# LoRa-Alarm.net
KiCad netlist of a schematic drawn in Altium Designer
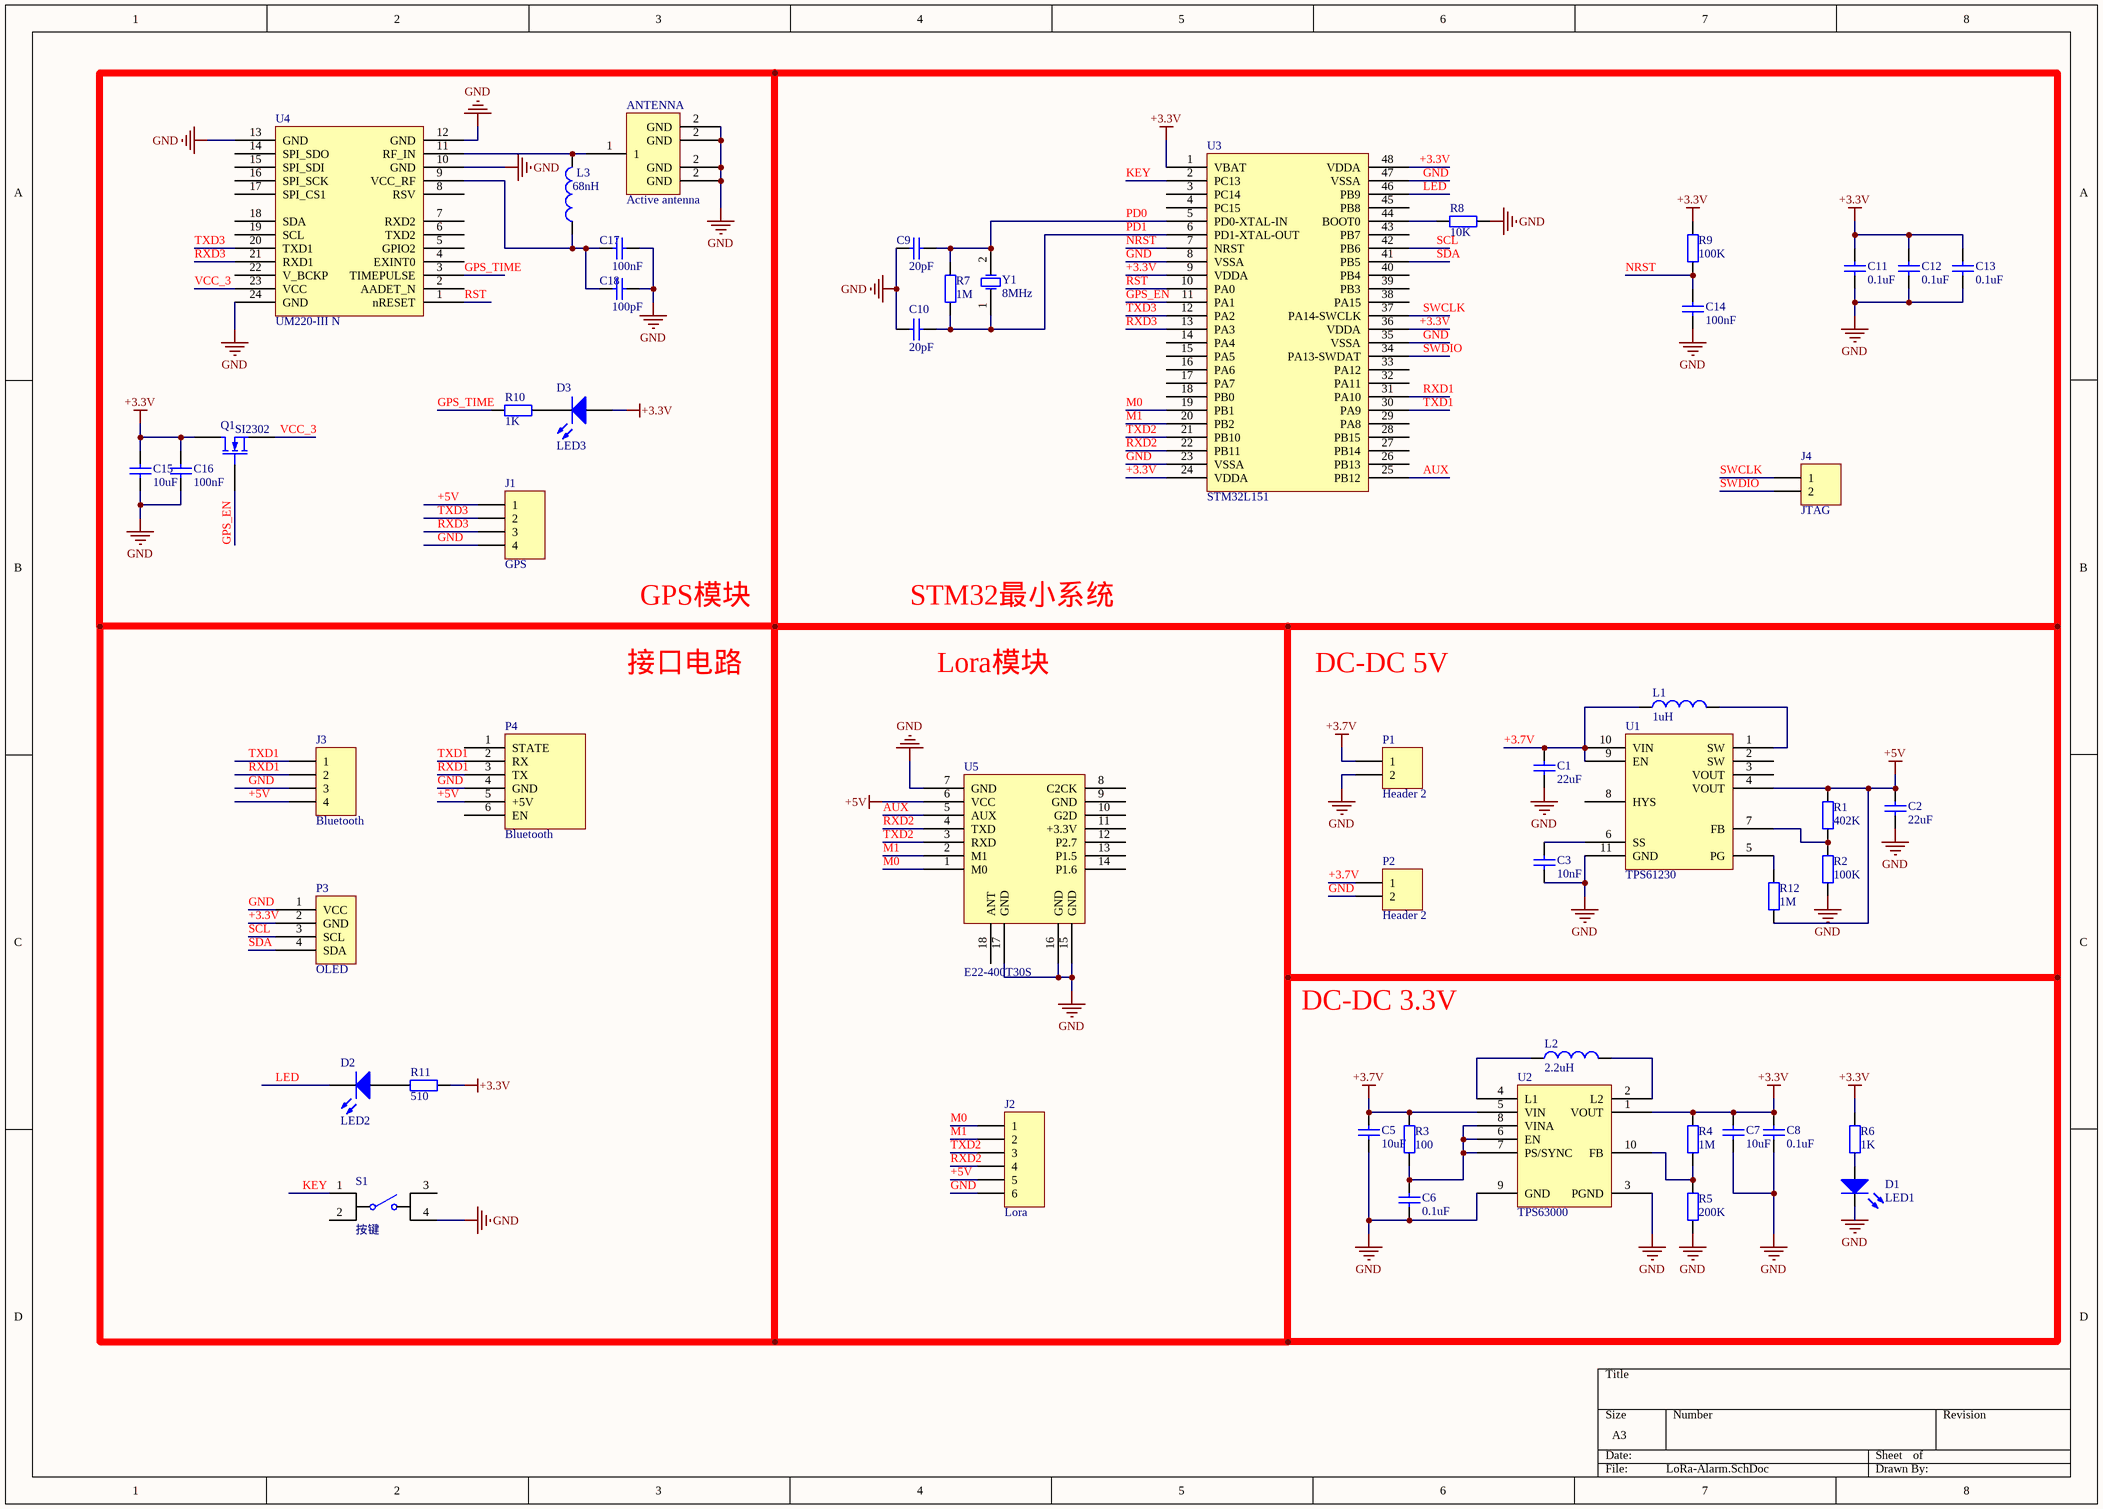
[diagram p0: LoRa-Alarm.SchDoc]

(export (version "E")
  (design (tool "Eeschema 10.0.6"))
  (components
    (comp (ref "ANTENNA")
      (value "Active antenna")
      (footprint "SMA-W")
      (libsource (lib "WuRenSouJiu") (part "Active antenna"))
    )
    (comp (ref "C1")
      (value "22uF")
      (footprint "0603C")
      (description "Capacitor")
      (fields (field (name "Comment") "Cap1") (field (name "PUBLISHER") "Altium Limited"))
      (libsource (lib "Miscellaneous Devices") (part "Cap"))
    )
    (comp (ref "C2")
      (value "22uF")
      (footprint "0603C")
      (description "Capacitor")
      (fields (field (name "Comment") "Cap2") (field (name "PUBLISHER") "Altium Limited"))
      (libsource (lib "Miscellaneous Devices") (part "Cap"))
    )
    (comp (ref "C3")
      (value "10nF")
      (footprint "0603C")
      (description "Capacitor")
      (fields (field (name "Comment") "Cap3") (field (name "PUBLISHER") "Altium Limited"))
      (libsource (lib "Miscellaneous Devices") (part "Cap"))
    )
    (comp (ref "C5")
      (value "10uF")
      (footprint "0603C")
      (description "Capacitor")
      (fields (field (name "Comment") "Cap5") (field (name "PUBLISHER") "Altium Limited"))
      (libsource (lib "Miscellaneous Devices") (part "Cap"))
    )
    (comp (ref "C6")
      (value "0.1uF")
      (footprint "0603C")
      (description "Capacitor")
      (fields (field (name "Comment") "Cap6") (field (name "PUBLISHER") "Altium Limited"))
      (libsource (lib "Miscellaneous Devices") (part "Cap"))
    )
    (comp (ref "C7")
      (value "10uF")
      (footprint "0603C")
      (description "Capacitor")
      (fields (field (name "Comment") "Cap7") (field (name "PUBLISHER") "Altium Limited"))
      (libsource (lib "Miscellaneous Devices") (part "Cap"))
    )
    (comp (ref "C8")
      (value "0.1uF")
      (footprint "0603C")
      (description "Capacitor")
      (fields (field (name "Comment") "Cap8") (field (name "PUBLISHER") "Altium Limited"))
      (libsource (lib "Miscellaneous Devices") (part "Cap"))
    )
    (comp (ref "C9")
      (value "20pF")
      (footprint "0603C")
      (description "Capacitor")
      (fields (field (name "Comment") "Cap9") (field (name "PUBLISHER") "Altium Limited"))
      (libsource (lib "Miscellaneous Devices") (part "Cap"))
    )
    (comp (ref "C10")
      (value "20pF")
      (footprint "0603C")
      (description "Capacitor")
      (fields (field (name "Comment") "Cap10") (field (name "PUBLISHER") "Altium Limited"))
      (libsource (lib "Miscellaneous Devices") (part "Cap"))
    )
    (comp (ref "C11")
      (value "0.1uF")
      (footprint "0603C")
      (description "Capacitor")
      (fields (field (name "Comment") "Cap11") (field (name "PUBLISHER") "Altium Limited"))
      (libsource (lib "Miscellaneous Devices") (part "Cap"))
    )
    (comp (ref "C12")
      (value "0.1uF")
      (footprint "0603C")
      (description "Capacitor")
      (fields (field (name "Comment") "Cap12") (field (name "PUBLISHER") "Altium Limited"))
      (libsource (lib "Miscellaneous Devices") (part "Cap"))
    )
    (comp (ref "C13")
      (value "0.1uF")
      (footprint "0603C")
      (description "Capacitor")
      (fields (field (name "Comment") "Cap13") (field (name "PUBLISHER") "Altium Limited"))
      (libsource (lib "Miscellaneous Devices") (part "Cap"))
    )
    (comp (ref "C14")
      (value "100nF")
      (footprint "0603C")
      (description "Capacitor")
      (fields (field (name "Comment") "Cap14") (field (name "PUBLISHER") "Altium Limited"))
      (libsource (lib "Miscellaneous Devices") (part "Cap"))
    )
    (comp (ref "C15")
      (value "10uF")
      (footprint "0603C")
      (description "Capacitor")
      (fields (field (name "Comment") "Cap15") (field (name "PUBLISHER") "Altium Limited"))
      (libsource (lib "Miscellaneous Devices") (part "Cap"))
    )
    (comp (ref "C16")
      (value "100nF")
      (footprint "0603C")
      (description "Capacitor")
      (fields (field (name "Comment") "Cap16") (field (name "PUBLISHER") "Altium Limited"))
      (libsource (lib "Miscellaneous Devices") (part "Cap"))
    )
    (comp (ref "C17")
      (value "100nF")
      (footprint "0603C")
      (description "Capacitor")
      (fields (field (name "Comment") "Cap17") (field (name "PUBLISHER") "Altium Limited"))
      (libsource (lib "Miscellaneous Devices") (part "Cap"))
    )
    (comp (ref "C18")
      (value "100pF")
      (footprint "0603C")
      (description "Capacitor")
      (fields (field (name "Comment") "Cap18") (field (name "PUBLISHER") "Altium Limited"))
      (libsource (lib "Miscellaneous Devices") (part "Cap"))
    )
    (comp (ref "D1")
      (value "LED1")
      (footprint "贴片二极管")
      (description "Typical RED GaAs LED")
      (fields (field (name "PUBLISHER") "Altium Limited"))
      (libsource (lib "Miscellaneous Devices") (part "LED1"))
    )
    (comp (ref "D2")
      (value "LED2")
      (footprint "贴片二极管")
      (description "Typical RED GaAs LED")
      (fields (field (name "PUBLISHER") "Altium Limited"))
      (libsource (lib "Miscellaneous Devices") (part "LED1"))
    )
    (comp (ref "D3")
      (value "LED3")
      (footprint "贴片二极管")
      (description "Typical RED GaAs LED")
      (fields (field (name "PUBLISHER") "Altium Limited"))
      (libsource (lib "Miscellaneous Devices") (part "LED1"))
    )
    (comp (ref "J1")
      (value "GPS")
      (footprint "HDR1X4")
      (description "Header, 4-Pin")
      (fields (field (name "PUBLISHER") "Altium Limited"))
      (libsource (lib "Miscellaneous Connectors") (part "Header 4"))
    )
    (comp (ref "J2")
      (value "Lora")
      (footprint "HDR1X6")
      (description "Header, 6-Pin")
      (fields (field (name "PUBLISHER") "Altium Limited"))
      (libsource (lib "Miscellaneous Connectors") (part "Header 6"))
    )
    (comp (ref "J3")
      (value "Bluetooth")
      (footprint "HDR1X4")
      (description "Header, 4-Pin")
      (fields (field (name "PUBLISHER") "Altium Limited"))
      (libsource (lib "Miscellaneous Connectors") (part "Header 4"))
    )
    (comp (ref "J4")
      (value "JTAG")
      (footprint "HDR1X2")
      (description "Header, 2-Pin")
      (fields (field (name "PUBLISHER") "Altium Limited"))
      (libsource (lib "Miscellaneous Connectors") (part "Header 2"))
    )
    (comp (ref "L1")
      (value "1uH")
      (footprint "IND-SMD_L4.0-W4.0_SMNR4020")
      (description "Inductor")
      (fields (field (name "Comment") "Inductor1") (field (name "PUBLISHER") "Altium Limited"))
      (libsource (lib "Miscellaneous Devices") (part "Inductor"))
    )
    (comp (ref "L2")
      (value "2.2uH")
      (footprint "IND-SMD_L4.0-W4.0_SMNR4020")
      (description "Inductor")
      (fields (field (name "Comment") "Inductor2") (field (name "PUBLISHER") "Altium Limited"))
      (libsource (lib "Miscellaneous Devices") (part "Inductor"))
    )
    (comp (ref "L3")
      (value "68nH")
      (footprint "0603L")
      (description "Inductor")
      (fields (field (name "Comment") "Inductor3") (field (name "PUBLISHER") "Altium Limited"))
      (libsource (lib "Miscellaneous Devices") (part "Inductor"))
    )
    (comp (ref "P1")
      (value "Header 2")
      (footprint "HDR1X2")
      (description "Header, 2-Pin")
      (fields (field (name "PUBLISHER") "Altium Limited"))
      (libsource (lib "Miscellaneous Connectors") (part "Header 2"))
    )
    (comp (ref "P2")
      (value "Header 2")
      (footprint "HDR1X2")
      (description "Header, 2-Pin")
      (fields (field (name "PUBLISHER") "Altium Limited"))
      (libsource (lib "Miscellaneous Connectors") (part "Header 2"))
    )
    (comp (ref "P3") (value "OLED") (footprint "SIP4") (libsource (lib "WuRenSouJiu") (part "OLED")))
    (comp (ref "P4")
      (value "Bluetooth")
      (footprint "SIP6")
      (libsource (lib "WuRenSouJiu") (part "Bluetooth"))
    )
    (comp (ref "Q1")
      (value "SI2302")
      (footprint "SOT-23")
      (description "N-Channel MOSFET")
      (fields (field (name "PUBLISHER") "Altium Limited"))
      (libsource (lib "Miscellaneous Devices") (part "MOSFET-N"))
    )
    (comp (ref "R1")
      (value "402K")
      (footprint "0603R")
      (description "Resistor")
      (fields (field (name "Comment") "Res1") (field (name "PUBLISHER") "Altium Limited"))
      (libsource (lib "Miscellaneous Devices") (part "Res2"))
    )
    (comp (ref "R2")
      (value "100K")
      (footprint "0603R")
      (description "Resistor")
      (fields (field (name "Comment") "Res2") (field (name "PUBLISHER") "Altium Limited"))
      (libsource (lib "Miscellaneous Devices") (part "Res2"))
    )
    (comp (ref "R3")
      (value "100")
      (footprint "0603R")
      (description "Resistor")
      (fields (field (name "Comment") "Res3") (field (name "PUBLISHER") "Altium Limited"))
      (libsource (lib "Miscellaneous Devices") (part "Res2"))
    )
    (comp (ref "R4")
      (value "1M")
      (footprint "0603R")
      (description "Resistor")
      (fields (field (name "Comment") "Res4") (field (name "PUBLISHER") "Altium Limited"))
      (libsource (lib "Miscellaneous Devices") (part "Res2"))
    )
    (comp (ref "R5")
      (value "200K")
      (footprint "0603R")
      (description "Resistor")
      (fields (field (name "Comment") "Res5") (field (name "PUBLISHER") "Altium Limited"))
      (libsource (lib "Miscellaneous Devices") (part "Res2"))
    )
    (comp (ref "R6")
      (value "1K")
      (footprint "0603R")
      (description "Resistor")
      (fields (field (name "Comment") "Res6") (field (name "PUBLISHER") "Altium Limited"))
      (libsource (lib "Miscellaneous Devices") (part "Res2"))
    )
    (comp (ref "R7")
      (value "1M")
      (footprint "0603R")
      (description "Resistor")
      (fields (field (name "Comment") "Res7") (field (name "PUBLISHER") "Altium Limited"))
      (libsource (lib "Miscellaneous Devices") (part "Res2"))
    )
    (comp (ref "R8")
      (value "10K")
      (footprint "0603R")
      (description "Resistor")
      (fields (field (name "Comment") "Res8") (field (name "PUBLISHER") "Altium Limited"))
      (libsource (lib "") (part "Res2_1"))
    )
    (comp (ref "R9")
      (value "100K")
      (footprint "0603R")
      (description "Resistor")
      (fields (field (name "Comment") "Res9") (field (name "PUBLISHER") "Altium Limited"))
      (libsource (lib "Miscellaneous Devices") (part "Res2"))
    )
    (comp (ref "R10")
      (value "1K")
      (footprint "0603R")
      (description "Resistor")
      (fields (field (name "Comment") "Res10") (field (name "PUBLISHER") "Altium Limited"))
      (libsource (lib "") (part "Res2_2"))
    )
    (comp (ref "R11")
      (value "510")
      (footprint "0603R")
      (description "Resistor")
      (fields (field (name "Comment") "Res11") (field (name "PUBLISHER") "Altium Limited"))
      (libsource (lib "") (part "Res2_2"))
    )
    (comp (ref "R12")
      (value "1M")
      (footprint "0603R")
      (description "Resistor")
      (fields (field (name "Comment") "Res12") (field (name "PUBLISHER") "Altium Limited"))
      (libsource (lib "Miscellaneous Devices") (part "Res2"))
    )
    (comp (ref "S1")
      (value "按键")
      (footprint "KEY-SMD_4P-L6.0-W6.0-P3.90-LS10.0")
      (libsource (lib "WuRenSouJiu") (part "按键"))
    )
    (comp (ref "U1")
      (value "TPS61230")
      (footprint "VSON-10_L3.0-W3.0-P0.50-BL-EP")
      (libsource (lib "WuRenSouJiu") (part "TPS61230"))
    )
    (comp (ref "U2")
      (value "TPS63000")
      (footprint "SON-10_L3.1-W3.1-P0.50-BL-EP")
      (libsource (lib "WuRenSouJiu") (part "TPS63000"))
    )
    (comp (ref "U3")
      (value "STM32L151")
      (footprint "TQFP48")
      (libsource (lib "WuRenSouJiu") (part "STM32L151"))
    )
    (comp (ref "U4")
      (value "UM220-III N")
      (footprint "UM220-III N")
      (libsource (lib "WuRenSouJiu") (part "UM220-III N"))
    )
    (comp (ref "U5")
      (value "E22-400T30S")
      (footprint "PE32(915T30S)")
      (libsource (lib "WuRenSouJiu") (part "E22-400T30S"))
    )
    (comp (ref "Y1")
      (value "8MHz")
      (footprint "XTAL")
      (description "Crystal Oscillator")
      (fields (field (name "PUBLISHER") "Altium Limited"))
      (libsource (lib "Miscellaneous Devices") (part "XTAL"))
    )
  )
  (nets
    (net (code "1") (name "+3.3V") (class "Default")
      (node (ref "C11") (pin "1") (pinfunction "1_1") (pintype "passive"))
      (node (ref "C12") (pin "1") (pinfunction "1_1") (pintype "passive"))
      (node (ref "C13") (pin "1") (pinfunction "1_1") (pintype "passive"))
      (node (ref "C15") (pin "1") (pinfunction "1_1") (pintype "passive"))
      (node (ref "C16") (pin "1") (pinfunction "1_1") (pintype "passive"))
      (node (ref "C7") (pin "2") (pinfunction "2_2") (pintype "passive"))
      (node (ref "C8") (pin "2") (pinfunction "2_2") (pintype "passive"))
      (node (ref "D3") (pin "1") (pinfunction "A_1") (pintype "passive"))
      (node (ref "P3") (pin "2") (pinfunction "GND_2") (pintype "passive"))
      (node (ref "Q1") (pin "1") (pinfunction "D_1") (pintype "passive"))
      (node (ref "R11") (pin "1") (pinfunction "1_1") (pintype "passive"))
      (node (ref "R4") (pin "2") (pinfunction "2_2") (pintype "passive"))
      (node (ref "R6") (pin "2") (pinfunction "2_2") (pintype "passive"))
      (node (ref "R9") (pin "2") (pinfunction "2_2") (pintype "passive"))
      (node (ref "U2") (pin "1") (pinfunction "VOUT_1") (pintype "passive"))
      (node (ref "U3") (pin "1") (pinfunction "VBAT_1") (pintype "passive"))
      (node (ref "U3") (pin "24") (pinfunction "VDDA_24") (pintype "passive"))
      (node (ref "U3") (pin "36") (pinfunction "VDDA_36") (pintype "passive"))
      (node (ref "U3") (pin "48") (pinfunction "VDDA_48") (pintype "passive"))
      (node (ref "U3") (pin "9") (pinfunction "VDDA_9") (pintype "passive"))
    )
    (net (code "2") (name "+3.7V") (class "Default")
      (node (ref "C1") (pin "2") (pinfunction "2_2") (pintype "passive"))
      (node (ref "C5") (pin "2") (pinfunction "2_2") (pintype "passive"))
      (node (ref "L1") (pin "1") (pinfunction "1_1") (pintype "passive"))
      (node (ref "P1") (pin "1") (pinfunction "1_1") (pintype "passive"))
      (node (ref "P2") (pin "1") (pinfunction "1_1") (pintype "passive"))
      (node (ref "R3") (pin "2") (pinfunction "2_2") (pintype "passive"))
      (node (ref "U1") (pin "10") (pinfunction "VIN_10") (pintype "passive"))
      (node (ref "U1") (pin "9") (pinfunction "EN_9") (pintype "passive"))
      (node (ref "U2") (pin "5") (pinfunction "VIN_5") (pintype "passive"))
    )
    (net (code "3") (name "+5V") (class "Default")
      (node (ref "C2") (pin "2") (pinfunction "2_2") (pintype "passive"))
      (node (ref "J1") (pin "1") (pinfunction "1_1") (pintype "passive"))
      (node (ref "J2") (pin "5") (pinfunction "5_5") (pintype "passive"))
      (node (ref "J3") (pin "4") (pinfunction "4_4") (pintype "passive"))
      (node (ref "P4") (pin "5") (pinfunction "+5V_5") (pintype "passive"))
      (node (ref "R1") (pin "2") (pinfunction "2_2") (pintype "passive"))
      (node (ref "R12") (pin "1") (pinfunction "1_1") (pintype "passive"))
      (node (ref "U1") (pin "4") (pinfunction "VOUT_4") (pintype "passive"))
      (node (ref "U5") (pin "6") (pinfunction "VCC_6") (pintype "passive"))
    )
    (net (code "4") (name "/AUX") (class "Default")
      (node (ref "U3") (pin "25") (pinfunction "PB12_25") (pintype "passive"))
      (node (ref "U5") (pin "5") (pinfunction "AUX_5") (pintype "passive"))
    )
    (net (code "5") (name "/GPS_EN") (class "Default")
      (node (ref "Q1") (pin "2") (pinfunction "G_2") (pintype "passive"))
      (node (ref "U3") (pin "11") (pinfunction "PA1_11") (pintype "passive"))
    )
    (net (code "6") (name "/GPS_TIME") (class "Default")
      (node (ref "R10") (pin "2") (pinfunction "2_2") (pintype "passive"))
      (node (ref "U4") (pin "3") (pinfunction "TIMEPULSE_3") (pintype "passive"))
    )
    (net (code "7") (name "/KEY") (class "Default")
      (node (ref "S1") (pin "1") (pinfunction "COMMON_1") (pintype "passive"))
      (node (ref "U3") (pin "2") (pinfunction "PC13_2") (pintype "passive"))
    )
    (net (code "8") (name "/LED") (class "Default")
      (node (ref "D2") (pin "2") (pinfunction "K_2") (pintype "passive"))
      (node (ref "U3") (pin "46") (pinfunction "PB9_46") (pintype "passive"))
    )
    (net (code "9") (name "/M0") (class "Default")
      (node (ref "J2") (pin "1") (pinfunction "1_1") (pintype "passive"))
      (node (ref "U3") (pin "19") (pinfunction "PB1_19") (pintype "passive"))
      (node (ref "U5") (pin "1") (pinfunction "M0_1") (pintype "passive"))
    )
    (net (code "10") (name "/M1") (class "Default")
      (node (ref "J2") (pin "2") (pinfunction "2_2") (pintype "passive"))
      (node (ref "U3") (pin "20") (pinfunction "PB2_20") (pintype "passive"))
      (node (ref "U5") (pin "2") (pinfunction "M1_2") (pintype "passive"))
    )
    (net (code "11") (name "/NRST") (class "Default")
      (node (ref "C14") (pin "1") (pinfunction "1_1") (pintype "passive"))
      (node (ref "R9") (pin "1") (pinfunction "1_1") (pintype "passive"))
      (node (ref "U3") (pin "7") (pinfunction "NRST_7") (pintype "passive"))
    )
    (net (code "12") (name "/PD0") (class "Default")
      (node (ref "C9") (pin "1") (pinfunction "1_1") (pintype "passive"))
      (node (ref "R7") (pin "2") (pinfunction "2_2") (pintype "passive"))
      (node (ref "U3") (pin "5") (pinfunction "PD0-XTAL-IN_5") (pintype "passive"))
      (node (ref "Y1") (pin "2") (pinfunction "OSC2_2") (pintype "passive"))
    )
    (net (code "13") (name "/PD1") (class "Default")
      (node (ref "C10") (pin "1") (pinfunction "1_1") (pintype "passive"))
      (node (ref "R7") (pin "1") (pinfunction "1_1") (pintype "passive"))
      (node (ref "U3") (pin "6") (pinfunction "PD1-XTAL-OUT_6") (pintype "passive"))
      (node (ref "Y1") (pin "1") (pinfunction "OSC1_1") (pintype "passive"))
    )
    (net (code "14") (name "/RST") (class "Default")
      (node (ref "U3") (pin "10") (pinfunction "PA0_10") (pintype "passive"))
      (node (ref "U4") (pin "1") (pinfunction "nRESET_1") (pintype "passive"))
    )
    (net (code "15") (name "/RXD1") (class "Default")
      (node (ref "J3") (pin "2") (pinfunction "2_2") (pintype "passive"))
      (node (ref "P4") (pin "3") (pinfunction "TX_3") (pintype "passive"))
      (node (ref "U3") (pin "31") (pinfunction "PA10_31") (pintype "passive"))
    )
    (net (code "16") (name "/RXD2") (class "Default")
      (node (ref "J2") (pin "4") (pinfunction "4_4") (pintype "passive"))
      (node (ref "U3") (pin "22") (pinfunction "PB11_22") (pintype "passive"))
      (node (ref "U5") (pin "4") (pinfunction "TXD_4") (pintype "passive"))
    )
    (net (code "17") (name "/RXD3") (class "Default")
      (node (ref "J1") (pin "3") (pinfunction "3_3") (pintype "passive"))
      (node (ref "U3") (pin "13") (pinfunction "PA3_13") (pintype "passive"))
      (node (ref "U4") (pin "21") (pinfunction "RXD1_21") (pintype "passive"))
    )
    (net (code "18") (name "/SCL") (class "Default")
      (node (ref "P3") (pin "3") (pinfunction "SCL_3") (pintype "passive"))
      (node (ref "U3") (pin "42") (pinfunction "PB6_42") (pintype "passive"))
    )
    (net (code "19") (name "/SDA") (class "Default")
      (node (ref "P3") (pin "4") (pinfunction "SDA_4") (pintype "passive"))
      (node (ref "U3") (pin "41") (pinfunction "PB5_41") (pintype "passive"))
    )
    (net (code "20") (name "/SWCLK") (class "Default")
      (node (ref "J4") (pin "1") (pinfunction "1_1") (pintype "passive"))
      (node (ref "U3") (pin "37") (pinfunction "PA14-SWCLK_37") (pintype "passive"))
    )
    (net (code "21") (name "/SWDIO") (class "Default")
      (node (ref "J4") (pin "2") (pinfunction "2_2") (pintype "passive"))
      (node (ref "U3") (pin "34") (pinfunction "PA13-SWDAT_34") (pintype "passive"))
    )
    (net (code "22") (name "/TXD1") (class "Default")
      (node (ref "J3") (pin "1") (pinfunction "1_1") (pintype "passive"))
      (node (ref "P4") (pin "2") (pinfunction "RX_2") (pintype "passive"))
      (node (ref "U3") (pin "30") (pinfunction "PA9_30") (pintype "passive"))
    )
    (net (code "23") (name "/TXD2") (class "Default")
      (node (ref "J2") (pin "3") (pinfunction "3_3") (pintype "passive"))
      (node (ref "U3") (pin "21") (pinfunction "PB10_21") (pintype "passive"))
      (node (ref "U5") (pin "3") (pinfunction "RXD_3") (pintype "passive"))
    )
    (net (code "24") (name "/TXD3") (class "Default")
      (node (ref "J1") (pin "2") (pinfunction "2_2") (pintype "passive"))
      (node (ref "U3") (pin "12") (pinfunction "PA2_12") (pintype "passive"))
      (node (ref "U4") (pin "20") (pinfunction "TXD1_20") (pintype "passive"))
    )
    (net (code "25") (name "/VCC_3") (class "Default")
      (node (ref "Q1") (pin "3") (pinfunction "S_3") (pintype "passive"))
      (node (ref "U4") (pin "23") (pinfunction "VCC_23") (pintype "passive"))
    )
    (net (code "26") (name "GND") (class "Default")
      (node (ref "ANTENNA") (pin "2") (pinfunction "GND_2") (pintype "passive"))
      (node (ref "C1") (pin "1") (pinfunction "1_1") (pintype "passive"))
      (node (ref "C10") (pin "2") (pinfunction "2_2") (pintype "passive"))
      (node (ref "C11") (pin "2") (pinfunction "2_2") (pintype "passive"))
      (node (ref "C12") (pin "2") (pinfunction "2_2") (pintype "passive"))
      (node (ref "C13") (pin "2") (pinfunction "2_2") (pintype "passive"))
      (node (ref "C14") (pin "2") (pinfunction "2_2") (pintype "passive"))
      (node (ref "C15") (pin "2") (pinfunction "2_2") (pintype "passive"))
      (node (ref "C16") (pin "2") (pinfunction "2_2") (pintype "passive"))
      (node (ref "C17") (pin "2") (pinfunction "2_2") (pintype "passive"))
      (node (ref "C18") (pin "2") (pinfunction "2_2") (pintype "passive"))
      (node (ref "C2") (pin "1") (pinfunction "1_1") (pintype "passive"))
      (node (ref "C3") (pin "1") (pinfunction "1_1") (pintype "passive"))
      (node (ref "C5") (pin "1") (pinfunction "1_1") (pintype "passive"))
      (node (ref "C6") (pin "1") (pinfunction "1_1") (pintype "passive"))
      (node (ref "C7") (pin "1") (pinfunction "1_1") (pintype "passive"))
      (node (ref "C8") (pin "1") (pinfunction "1_1") (pintype "passive"))
      (node (ref "C9") (pin "2") (pinfunction "2_2") (pintype "passive"))
      (node (ref "D1") (pin "2") (pinfunction "K_2") (pintype "passive"))
      (node (ref "J1") (pin "4") (pinfunction "4_4") (pintype "passive"))
      (node (ref "J2") (pin "6") (pinfunction "6_6") (pintype "passive"))
      (node (ref "J3") (pin "3") (pinfunction "3_3") (pintype "passive"))
      (node (ref "P1") (pin "2") (pinfunction "2_2") (pintype "passive"))
      (node (ref "P2") (pin "2") (pinfunction "2_2") (pintype "passive"))
      (node (ref "P3") (pin "1") (pinfunction "VCC_1") (pintype "passive"))
      (node (ref "P4") (pin "4") (pinfunction "GND_4") (pintype "passive"))
      (node (ref "R2") (pin "1") (pinfunction "1_1") (pintype "passive"))
      (node (ref "R5") (pin "1") (pinfunction "1_1") (pintype "passive"))
      (node (ref "R8") (pin "2") (pinfunction "2_2") (pintype "passive"))
      (node (ref "S1") (pin "4") (pinfunction "COMMON_4") (pintype "passive"))
      (node (ref "U1") (pin "11") (pinfunction "GND_11") (pintype "passive"))
      (node (ref "U2") (pin "3") (pinfunction "PGND_3") (pintype "passive"))
      (node (ref "U2") (pin "9") (pinfunction "GND_9") (pintype "passive"))
      (node (ref "U3") (pin "23") (pinfunction "VSSA_23") (pintype "passive"))
      (node (ref "U3") (pin "35") (pinfunction "VSSA_35") (pintype "passive"))
      (node (ref "U3") (pin "47") (pinfunction "VSSA_47") (pintype "passive"))
      (node (ref "U3") (pin "8") (pinfunction "VSSA_8") (pintype "passive"))
      (node (ref "U4") (pin "10") (pinfunction "GND_10") (pintype "passive"))
      (node (ref "U4") (pin "12") (pinfunction "GND_12") (pintype "passive"))
      (node (ref "U4") (pin "13") (pinfunction "GND_13") (pintype "passive"))
      (node (ref "U4") (pin "24") (pinfunction "GND_24") (pintype "passive"))
      (node (ref "U5") (pin "15") (pinfunction "GND_15") (pintype "passive"))
      (node (ref "U5") (pin "16") (pinfunction "GND_16") (pintype "passive"))
      (node (ref "U5") (pin "17") (pinfunction "GND_17") (pintype "passive"))
      (node (ref "U5") (pin "7") (pinfunction "GND_7") (pintype "passive"))
    )
    (net (code "27") (name "Net-(D1-A)") (class "Default")
      (node (ref "D1") (pin "1") (pinfunction "A_1") (pintype "passive"))
      (node (ref "R6") (pin "1") (pinfunction "1_1") (pintype "passive"))
    )
    (net (code "28") (name "Net-(D2-A)") (class "Default")
      (node (ref "D2") (pin "1") (pinfunction "A_1") (pintype "passive"))
      (node (ref "R11") (pin "2") (pinfunction "2_2") (pintype "passive"))
    )
    (net (code "29") (name "Net-(D3-K)") (class "Default")
      (node (ref "D3") (pin "2") (pinfunction "K_2") (pintype "passive"))
      (node (ref "R10") (pin "1") (pinfunction "1_1") (pintype "passive"))
    )
    (net (code "30") (name "Net-(L1-Pad2)") (class "Default")
      (node (ref "L1") (pin "2") (pinfunction "2_2") (pintype "passive"))
      (node (ref "U1") (pin "1") (pinfunction "SW_1") (pintype "passive"))
    )
    (net (code "31") (name "Net-(U1-FB)") (class "Default")
      (node (ref "R1") (pin "1") (pinfunction "1_1") (pintype "passive"))
      (node (ref "R2") (pin "2") (pinfunction "2_2") (pintype "passive"))
      (node (ref "U1") (pin "7") (pinfunction "FB_7") (pintype "passive"))
    )
    (net (code "32") (name "Net-(U1-PG)") (class "Default")
      (node (ref "R12") (pin "2") (pinfunction "2_2") (pintype "passive"))
      (node (ref "U1") (pin "5") (pinfunction "PG_5") (pintype "passive"))
    )
    (net (code "33") (name "Net-(U1-SS)") (class "Default")
      (node (ref "C3") (pin "2") (pinfunction "2_2") (pintype "passive"))
      (node (ref "U1") (pin "6") (pinfunction "SS_6") (pintype "passive"))
    )
    (net (code "34") (name "Net-(U2-EN)") (class "Default")
      (node (ref "C6") (pin "2") (pinfunction "2_2") (pintype "passive"))
      (node (ref "R3") (pin "1") (pinfunction "1_1") (pintype "passive"))
      (node (ref "U2") (pin "6") (pinfunction "EN_6") (pintype "passive"))
      (node (ref "U2") (pin "7") (pinfunction "PS/SYNC_7") (pintype "passive"))
      (node (ref "U2") (pin "8") (pinfunction "VINA_8") (pintype "passive"))
    )
    (net (code "35") (name "Net-(U2-FB)") (class "Default")
      (node (ref "R4") (pin "1") (pinfunction "1_1") (pintype "passive"))
      (node (ref "R5") (pin "2") (pinfunction "2_2") (pintype "passive"))
      (node (ref "U2") (pin "10") (pinfunction "FB_10") (pintype "passive"))
    )
    (net (code "36") (name "Net-(U2-L1)") (class "Default")
      (node (ref "L2") (pin "1") (pinfunction "1_1") (pintype "passive"))
      (node (ref "U2") (pin "4") (pinfunction "L1_4") (pintype "passive"))
    )
    (net (code "37") (name "Net-(U2-L2)") (class "Default")
      (node (ref "L2") (pin "2") (pinfunction "2_2") (pintype "passive"))
      (node (ref "U2") (pin "2") (pinfunction "L2_2") (pintype "passive"))
    )
    (net (code "38") (name "Net-(U3-BOOT0)") (class "Default")
      (node (ref "R8") (pin "1") (pinfunction "1_1") (pintype "passive"))
      (node (ref "U3") (pin "44") (pinfunction "BOOT0_44") (pintype "passive"))
    )
    (net (code "39") (name "Net-(U4-RF_IN)") (class "Default")
      (node (ref "ANTENNA") (pin "1") (pinfunction "1_1") (pintype "passive"))
      (node (ref "L3") (pin "2") (pinfunction "2_2") (pintype "passive"))
      (node (ref "U4") (pin "11") (pinfunction "RF_IN_11") (pintype "passive"))
    )
    (net (code "40") (name "Net-(U4-VCC_RF)") (class "Default")
      (node (ref "C17") (pin "1") (pinfunction "1_1") (pintype "passive"))
      (node (ref "C18") (pin "1") (pinfunction "1_1") (pintype "passive"))
      (node (ref "L3") (pin "1") (pinfunction "1_1") (pintype "passive"))
      (node (ref "U4") (pin "9") (pinfunction "VCC_RF_9") (pintype "passive"))
    )
    (net (code "41") (name "unconnected-(P4-EN-Pad6)") (class "Default")
      (node (ref "P4") (pin "6") (pinfunction "EN_6") (pintype "passive"))
    )
    (net (code "42") (name "unconnected-(P4-STATE-Pad1)") (class "Default")
      (node (ref "P4") (pin "1") (pinfunction "STATE_1") (pintype "passive"))
    )
    (net (code "43") (name "unconnected-(S1-COMMON-Pad2)") (class "Default")
      (node (ref "S1") (pin "2") (pinfunction "COMMON_2") (pintype "passive"))
    )
    (net (code "44") (name "unconnected-(S1-Pad3)") (class "Default")
      (node (ref "S1") (pin "3") (pintype "passive"))
    )
    (net (code "45") (name "unconnected-(U1-HYS-Pad8)") (class "Default")
      (node (ref "U1") (pin "8") (pinfunction "HYS_8") (pintype "passive"))
    )
    (net (code "46") (name "unconnected-(U1-SW-Pad2)") (class "Default")
      (node (ref "U1") (pin "2") (pinfunction "SW_2") (pintype "passive"))
    )
    (net (code "47") (name "unconnected-(U1-VOUT-Pad3)") (class "Default")
      (node (ref "U1") (pin "3") (pinfunction "VOUT_3") (pintype "passive"))
    )
    (net (code "48") (name "unconnected-(U3-PA4-Pad14)") (class "Default")
      (node (ref "U3") (pin "14") (pinfunction "PA4_14") (pintype "passive"))
    )
    (net (code "49") (name "unconnected-(U3-PA5-Pad15)") (class "Default")
      (node (ref "U3") (pin "15") (pinfunction "PA5_15") (pintype "passive"))
    )
    (net (code "50") (name "unconnected-(U3-PA6-Pad16)") (class "Default")
      (node (ref "U3") (pin "16") (pinfunction "PA6_16") (pintype "passive"))
    )
    (net (code "51") (name "unconnected-(U3-PA7-Pad17)") (class "Default")
      (node (ref "U3") (pin "17") (pinfunction "PA7_17") (pintype "passive"))
    )
    (net (code "52") (name "unconnected-(U3-PA8-Pad29)") (class "Default")
      (node (ref "U3") (pin "29") (pinfunction "PA8_29") (pintype "passive"))
    )
    (net (code "53") (name "unconnected-(U3-PA11-Pad32)") (class "Default")
      (node (ref "U3") (pin "32") (pinfunction "PA11_32") (pintype "passive"))
    )
    (net (code "54") (name "unconnected-(U3-PA12-Pad33)") (class "Default")
      (node (ref "U3") (pin "33") (pinfunction "PA12_33") (pintype "passive"))
    )
    (net (code "55") (name "unconnected-(U3-PA15-Pad38)") (class "Default")
      (node (ref "U3") (pin "38") (pinfunction "PA15_38") (pintype "passive"))
    )
    (net (code "56") (name "unconnected-(U3-PB0-Pad18)") (class "Default")
      (node (ref "U3") (pin "18") (pinfunction "PB0_18") (pintype "passive"))
    )
    (net (code "57") (name "unconnected-(U3-PB3-Pad39)") (class "Default")
      (node (ref "U3") (pin "39") (pinfunction "PB3_39") (pintype "passive"))
    )
    (net (code "58") (name "unconnected-(U3-PB4-Pad40)") (class "Default")
      (node (ref "U3") (pin "40") (pinfunction "PB4_40") (pintype "passive"))
    )
    (net (code "59") (name "unconnected-(U3-PB7-Pad43)") (class "Default")
      (node (ref "U3") (pin "43") (pinfunction "PB7_43") (pintype "passive"))
    )
    (net (code "60") (name "unconnected-(U3-PB8-Pad45)") (class "Default")
      (node (ref "U3") (pin "45") (pinfunction "PB8_45") (pintype "passive"))
    )
    (net (code "61") (name "unconnected-(U3-PB13-Pad26)") (class "Default")
      (node (ref "U3") (pin "26") (pinfunction "PB13_26") (pintype "passive"))
    )
    (net (code "62") (name "unconnected-(U3-PB14-Pad27)") (class "Default")
      (node (ref "U3") (pin "27") (pinfunction "PB14_27") (pintype "passive"))
    )
    (net (code "63") (name "unconnected-(U3-PB15-Pad28)") (class "Default")
      (node (ref "U3") (pin "28") (pinfunction "PB15_28") (pintype "passive"))
    )
    (net (code "64") (name "unconnected-(U3-PC14-Pad3)") (class "Default")
      (node (ref "U3") (pin "3") (pinfunction "PC14_3") (pintype "passive"))
    )
    (net (code "65") (name "unconnected-(U3-PC15-Pad4)") (class "Default")
      (node (ref "U3") (pin "4") (pinfunction "PC15_4") (pintype "passive"))
    )
    (net (code "66") (name "unconnected-(U4-AADET_N-Pad2)") (class "Default")
      (node (ref "U4") (pin "2") (pinfunction "AADET_N_2") (pintype "passive"))
    )
    (net (code "67") (name "unconnected-(U4-EXINT0-Pad4)") (class "Default")
      (node (ref "U4") (pin "4") (pinfunction "EXINT0_4") (pintype "passive"))
    )
    (net (code "68") (name "unconnected-(U4-GPIO2-Pad5)") (class "Default")
      (node (ref "U4") (pin "5") (pinfunction "GPIO2_5") (pintype "passive"))
    )
    (net (code "69") (name "unconnected-(U4-RSV-Pad8)") (class "Default")
      (node (ref "U4") (pin "8") (pinfunction "RSV_8") (pintype "passive"))
    )
    (net (code "70") (name "unconnected-(U4-RXD2-Pad7)") (class "Default")
      (node (ref "U4") (pin "7") (pinfunction "RXD2_7") (pintype "passive"))
    )
    (net (code "71") (name "unconnected-(U4-SCL-Pad19)") (class "Default")
      (node (ref "U4") (pin "19") (pinfunction "SCL_19") (pintype "passive"))
    )
    (net (code "72") (name "unconnected-(U4-SDA-Pad18)") (class "Default")
      (node (ref "U4") (pin "18") (pinfunction "SDA_18") (pintype "passive"))
    )
    (net (code "73") (name "unconnected-(U4-SPI_CS1-Pad17)") (class "Default")
      (node (ref "U4") (pin "17") (pinfunction "SPI_CS1_17") (pintype "passive"))
    )
    (net (code "74") (name "unconnected-(U4-SPI_SCK-Pad16)") (class "Default")
      (node (ref "U4") (pin "16") (pinfunction "SPI_SCK_16") (pintype "passive"))
    )
    (net (code "75") (name "unconnected-(U4-SPI_SDI-Pad15)") (class "Default")
      (node (ref "U4") (pin "15") (pinfunction "SPI_SDI_15") (pintype "passive"))
    )
    (net (code "76") (name "unconnected-(U4-SPI_SDO-Pad14)") (class "Default")
      (node (ref "U4") (pin "14") (pinfunction "SPI_SDO_14") (pintype "passive"))
    )
    (net (code "77") (name "unconnected-(U4-TXD2-Pad6)") (class "Default")
      (node (ref "U4") (pin "6") (pinfunction "TXD2_6") (pintype "passive"))
    )
    (net (code "78") (name "unconnected-(U4-V_BCKP-Pad22)") (class "Default")
      (node (ref "U4") (pin "22") (pinfunction "V_BCKP_22") (pintype "passive"))
    )
    (net (code "79") (name "unconnected-(U5-+3.3V-Pad11)") (class "Default")
      (node (ref "U5") (pin "11") (pinfunction "+3.3V_11") (pintype "passive"))
    )
    (net (code "80") (name "unconnected-(U5-ANT-Pad18)") (class "Default")
      (node (ref "U5") (pin "18") (pinfunction "ANT_18") (pintype "passive"))
    )
    (net (code "81") (name "unconnected-(U5-C2CK-Pad8)") (class "Default")
      (node (ref "U5") (pin "8") (pinfunction "C2CK_8") (pintype "passive"))
    )
    (net (code "82") (name "unconnected-(U5-G2D-Pad10)") (class "Default")
      (node (ref "U5") (pin "10") (pinfunction "G2D_10") (pintype "passive"))
    )
    (net (code "83") (name "unconnected-(U5-GND-Pad9)") (class "Default")
      (node (ref "U5") (pin "9") (pinfunction "GND_9") (pintype "passive"))
    )
    (net (code "84") (name "unconnected-(U5-P1.5-Pad13)") (class "Default")
      (node (ref "U5") (pin "13") (pinfunction "P1.5_13") (pintype "passive"))
    )
    (net (code "85") (name "unconnected-(U5-P1.6-Pad14)") (class "Default")
      (node (ref "U5") (pin "14") (pinfunction "P1.6_14") (pintype "passive"))
    )
    (net (code "86") (name "unconnected-(U5-P2.7-Pad12)") (class "Default")
      (node (ref "U5") (pin "12") (pinfunction "P2.7_12") (pintype "passive"))
    )
  )
)
